# PCM5102a.net
KiCad netlist of a schematic drawn in EAGLE
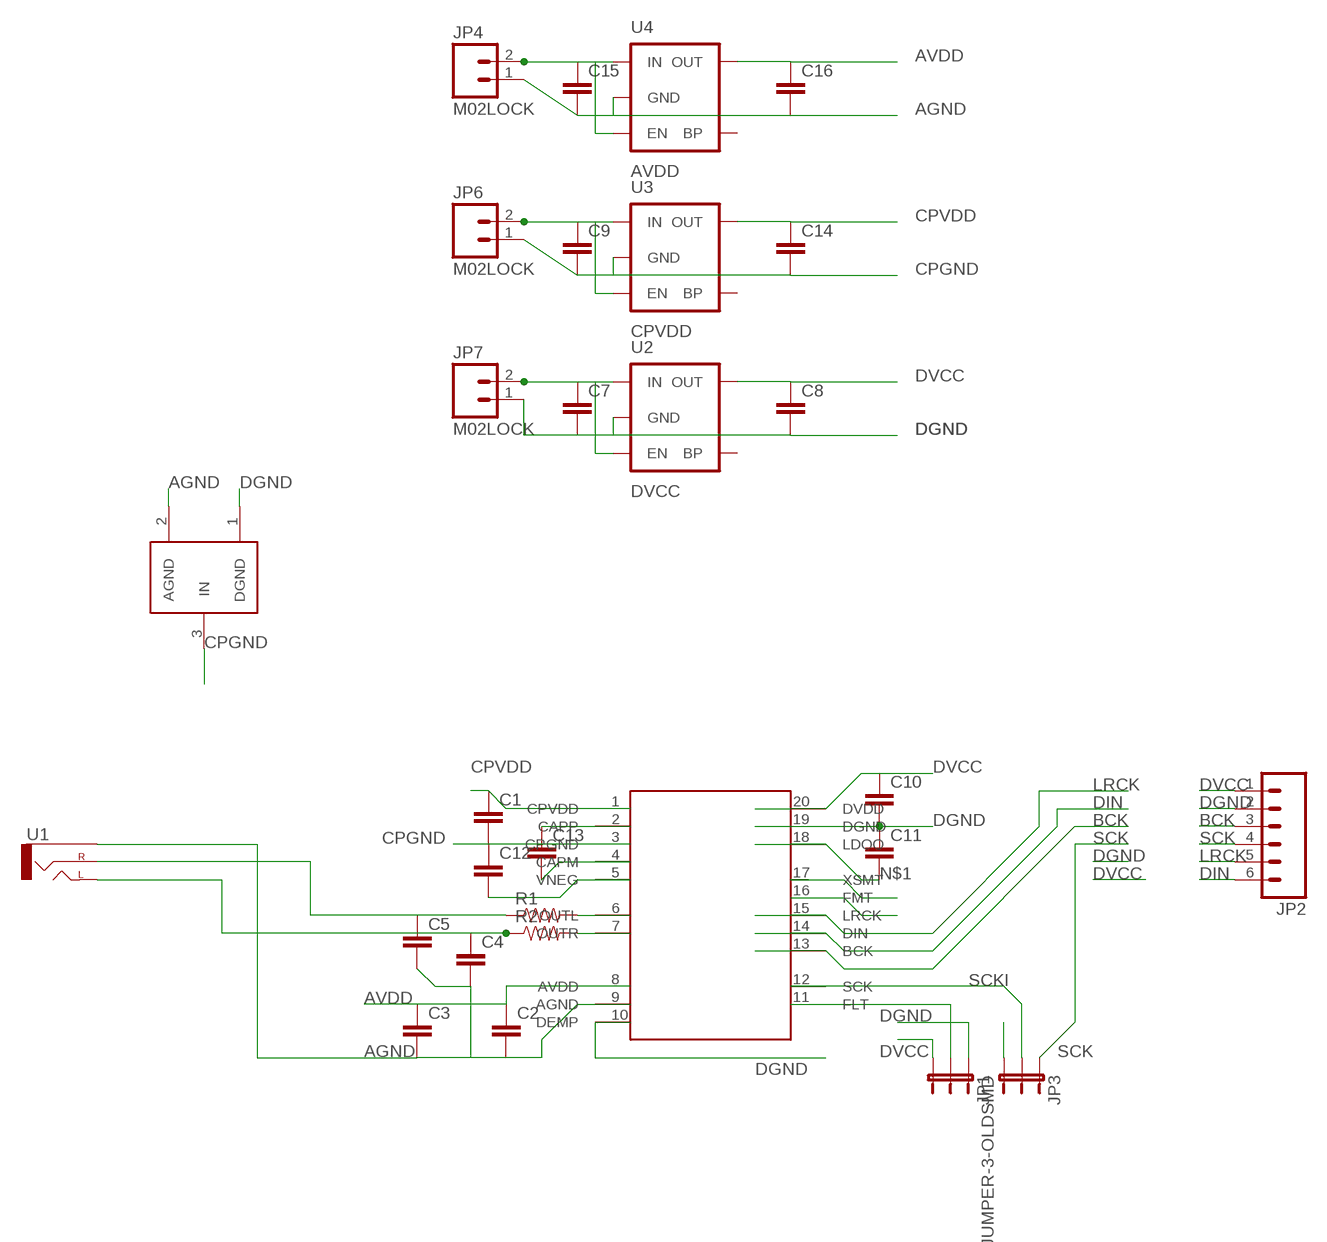
[diagram p0: schematic, sheet 1]

(export (version "E")
  (design (tool "Eeschema 10.0.6"))
  (components
    (comp (ref "C1")
      (value "CAP0805")
      (footprint "eagle-import:0805")
      (libsource (lib "eagle-import") (part "CAP0805"))
    )
    (comp (ref "C2")
      (value "CAP0805")
      (footprint "eagle-import:0805")
      (libsource (lib "eagle-import") (part "CAP0805"))
    )
    (comp (ref "C3")
      (value "CAP0805")
      (footprint "eagle-import:0805")
      (libsource (lib "eagle-import") (part "CAP0805"))
    )
    (comp (ref "C4")
      (value "CAPPTH1")
      (footprint "eagle-import:CAP-PTH-5MM")
      (libsource (lib "eagle-import") (part "CAPPTH1"))
    )
    (comp (ref "C5")
      (value "CAPPTH1")
      (footprint "eagle-import:CAP-PTH-5MM")
      (libsource (lib "eagle-import") (part "CAPPTH1"))
    )
    (comp (ref "C7")
      (value "CAP0805")
      (footprint "eagle-import:0805")
      (libsource (lib "eagle-import") (part "CAP0805"))
    )
    (comp (ref "C8")
      (value "CAP0805")
      (footprint "eagle-import:0805")
      (libsource (lib "eagle-import") (part "CAP0805"))
    )
    (comp (ref "C9")
      (value "CAP0805")
      (footprint "eagle-import:0805")
      (libsource (lib "eagle-import") (part "CAP0805"))
    )
    (comp (ref "C10")
      (value "CAP0805")
      (footprint "eagle-import:0805")
      (libsource (lib "eagle-import") (part "CAP0805"))
    )
    (comp (ref "C11")
      (value "CAP0805")
      (footprint "eagle-import:0805")
      (libsource (lib "eagle-import") (part "CAP0805"))
    )
    (comp (ref "C12")
      (value "CAP0805")
      (footprint "eagle-import:0805")
      (libsource (lib "eagle-import") (part "CAP0805"))
    )
    (comp (ref "C13")
      (value "CAP0805")
      (footprint "eagle-import:0805")
      (libsource (lib "eagle-import") (part "CAP0805"))
    )
    (comp (ref "C14")
      (value "CAP0805")
      (footprint "eagle-import:0805")
      (libsource (lib "eagle-import") (part "CAP0805"))
    )
    (comp (ref "C15")
      (value "CAP0805")
      (footprint "eagle-import:0805")
      (libsource (lib "eagle-import") (part "CAP0805"))
    )
    (comp (ref "C16")
      (value "CAP0805")
      (footprint "eagle-import:0805")
      (libsource (lib "eagle-import") (part "CAP0805"))
    )
    (comp (ref "JP1")
      (value "JUMPER-3-OLDPTH")
      (footprint "eagle-import:1X03")
      (libsource (lib "eagle-import") (part "JUMPER-3-OLDPTH"))
    )
    (comp (ref "JP2")
      (value "M06LOCK")
      (footprint "eagle-import:1X06_LOCK")
      (libsource (lib "eagle-import") (part "M06LOCK"))
    )
    (comp (ref "JP3")
      (value "JUMPER-3-OLDSMD")
      (footprint "eagle-import:SJ_3")
      (libsource (lib "eagle-import") (part "JUMPER-3-OLDSMD"))
    )
    (comp (ref "JP4")
      (value "M02LOCK")
      (footprint "eagle-import:1X02_LOCK")
      (libsource (lib "eagle-import") (part "M02LOCK"))
    )
    (comp (ref "JP6")
      (value "M02LOCK")
      (footprint "eagle-import:1X02_LOCK")
      (libsource (lib "eagle-import") (part "M02LOCK"))
    )
    (comp (ref "JP7")
      (value "M02LOCK")
      (footprint "eagle-import:1X02_LOCK")
      (libsource (lib "eagle-import") (part "M02LOCK"))
    )
    (comp (ref "R1")
      (value "RESISTORPTH-1/4W")
      (footprint "eagle-import:AXIAL-0.4")
      (libsource (lib "eagle-import") (part "RESISTORPTH-1/4W"))
    )
    (comp (ref "R2")
      (value "RESISTORPTH-1/4W")
      (footprint "eagle-import:AXIAL-0.4")
      (libsource (lib "eagle-import") (part "RESISTORPTH-1/4W"))
    )
    (comp (ref "U$1")
      (value "PCM5102")
      (footprint "eagle-import:TSSOP20")
      (libsource (lib "eagle-import") (part "PCM5102"))
    )
    (comp (ref "U$2")
      (value "GND_CONNECT")
      (footprint "eagle-import:GND_CONNECT")
      (libsource (lib "eagle-import") (part "GND_CONNECT"))
    )
    (comp (ref "U1")
      (value "AUDIO-JACKPTH")
      (footprint "eagle-import:AUDIO-JACK")
      (libsource (lib "eagle-import") (part "AUDIO-JACKPTH"))
    )
    (comp (ref "U2")
      (value "DVCC")
      (footprint "eagle-import:SOT23-5")
      (libsource (lib "eagle-import") (part "V_REG_LDOSMD"))
    )
    (comp (ref "U3")
      (value "CPVDD")
      (footprint "eagle-import:SOT23-5")
      (libsource (lib "eagle-import") (part "V_REG_LDOSMD"))
    )
    (comp (ref "U4")
      (value "AVDD")
      (footprint "eagle-import:SOT23-5")
      (libsource (lib "eagle-import") (part "V_REG_LDOSMD"))
    )
  )
  (nets
    (net (code "1") (name "/AGND") (class "Default")
      (node (ref "C15") (pin "2") (pinfunction "2_2") (pintype "passive"))
      (node (ref "C16") (pin "2") (pinfunction "2_2") (pintype "passive"))
      (node (ref "C2") (pin "2") (pinfunction "2_2") (pintype "passive"))
      (node (ref "C3") (pin "2") (pinfunction "2_2") (pintype "passive"))
      (node (ref "C4") (pin "2") (pinfunction "2_2") (pintype "passive"))
      (node (ref "C5") (pin "2") (pinfunction "2_2") (pintype "passive"))
      (node (ref "JP4") (pin "1") (pinfunction "1_1") (pintype "passive"))
      (node (ref "U$1") (pin "9") (pinfunction "AGND_9") (pintype "bidirectional"))
      (node (ref "U$2") (pin "2") (pinfunction "AGND_2") (pintype "bidirectional"))
      (node (ref "U1") (pin "SLEEVE") (pinfunction "SLEEVE_SLEEVE") (pintype "bidirectional"))
      (node (ref "U4") (pin "2") (pinfunction "GND_2") (pintype "input"))
    )
    (net (code "2") (name "/AVDD") (class "Default")
      (node (ref "C16") (pin "1") (pinfunction "1_1") (pintype "passive"))
      (node (ref "C2") (pin "1") (pinfunction "1_1") (pintype "passive"))
      (node (ref "C3") (pin "1") (pinfunction "1_1") (pintype "passive"))
      (node (ref "U$1") (pin "8") (pinfunction "AVDD_8") (pintype "bidirectional"))
      (node (ref "U4") (pin "5") (pinfunction "OUT_5") (pintype "passive"))
    )
    (net (code "3") (name "/BCK") (class "Default")
      (node (ref "JP2") (pin "3") (pinfunction "3_3") (pintype "passive"))
      (node (ref "U$1") (pin "13") (pinfunction "BCK_13") (pintype "bidirectional"))
    )
    (net (code "4") (name "/CPGND") (class "Default")
      (node (ref "C1") (pin "2") (pinfunction "2_2") (pintype "passive"))
      (node (ref "C12") (pin "1") (pinfunction "1_1") (pintype "passive"))
      (node (ref "C14") (pin "2") (pinfunction "2_2") (pintype "passive"))
      (node (ref "C9") (pin "2") (pinfunction "2_2") (pintype "passive"))
      (node (ref "JP6") (pin "1") (pinfunction "1_1") (pintype "passive"))
      (node (ref "U$1") (pin "3") (pinfunction "CPGND_3") (pintype "bidirectional"))
      (node (ref "U$2") (pin "3") (pinfunction "IN_3") (pintype "bidirectional"))
      (node (ref "U3") (pin "2") (pinfunction "GND_2") (pintype "input"))
    )
    (net (code "5") (name "/CPVDD") (class "Default")
      (node (ref "C1") (pin "1") (pinfunction "1_1") (pintype "passive"))
      (node (ref "C14") (pin "1") (pinfunction "1_1") (pintype "passive"))
      (node (ref "U$1") (pin "1") (pinfunction "CPVDD_1") (pintype "bidirectional"))
      (node (ref "U3") (pin "5") (pinfunction "OUT_5") (pintype "passive"))
    )
    (net (code "6") (name "/DGND") (class "Default")
      (node (ref "C10") (pin "2") (pinfunction "2_2") (pintype "passive"))
      (node (ref "C11") (pin "1") (pinfunction "1_1") (pintype "passive"))
      (node (ref "C7") (pin "2") (pinfunction "2_2") (pintype "passive"))
      (node (ref "C8") (pin "2") (pinfunction "2_2") (pintype "passive"))
      (node (ref "JP1") (pin "1") (pinfunction "1_1") (pintype "passive"))
      (node (ref "JP2") (pin "2") (pinfunction "2_2") (pintype "passive"))
      (node (ref "JP3") (pin "3") (pinfunction "3_3") (pintype "passive"))
      (node (ref "JP7") (pin "1") (pinfunction "1_1") (pintype "passive"))
      (node (ref "U$1") (pin "10") (pinfunction "DEMP_10") (pintype "bidirectional"))
      (node (ref "U$1") (pin "16") (pinfunction "FMT_16") (pintype "bidirectional"))
      (node (ref "U$1") (pin "19") (pinfunction "DGND_19") (pintype "bidirectional"))
      (node (ref "U$2") (pin "1") (pinfunction "DGND_1") (pintype "bidirectional"))
      (node (ref "U2") (pin "2") (pinfunction "GND_2") (pintype "input"))
    )
    (net (code "7") (name "/DIN") (class "Default")
      (node (ref "JP2") (pin "6") (pinfunction "6_6") (pintype "passive"))
      (node (ref "U$1") (pin "14") (pinfunction "DIN_14") (pintype "bidirectional"))
    )
    (net (code "8") (name "/DVCC") (class "Default")
      (node (ref "C10") (pin "1") (pinfunction "1_1") (pintype "passive"))
      (node (ref "C8") (pin "1") (pinfunction "1_1") (pintype "passive"))
      (node (ref "JP1") (pin "3") (pinfunction "3_3") (pintype "passive"))
      (node (ref "JP2") (pin "1") (pinfunction "1_1") (pintype "passive"))
      (node (ref "U$1") (pin "17") (pinfunction "XSMT_17") (pintype "bidirectional"))
      (node (ref "U$1") (pin "20") (pinfunction "DVDD_20") (pintype "bidirectional"))
      (node (ref "U2") (pin "5") (pinfunction "OUT_5") (pintype "passive"))
    )
    (net (code "9") (name "/LRCK") (class "Default")
      (node (ref "JP2") (pin "5") (pinfunction "5_5") (pintype "passive"))
      (node (ref "U$1") (pin "15") (pinfunction "LRCK_15") (pintype "bidirectional"))
    )
    (net (code "10") (name "/N$1") (class "Default")
      (node (ref "C11") (pin "2") (pinfunction "2_2") (pintype "passive"))
      (node (ref "U$1") (pin "18") (pinfunction "LDOO_18") (pintype "bidirectional"))
    )
    (net (code "11") (name "/SCK") (class "Default")
      (node (ref "JP2") (pin "4") (pinfunction "4_4") (pintype "passive"))
      (node (ref "JP3") (pin "1") (pinfunction "1_1") (pintype "passive"))
    )
    (net (code "12") (name "/SCKI") (class "Default")
      (node (ref "JP3") (pin "2") (pinfunction "2_2") (pintype "passive"))
      (node (ref "U$1") (pin "12") (pinfunction "SCK_12") (pintype "bidirectional"))
    )
    (net (code "13") (name "Net-(R1-1)") (class "Default")
      (node (ref "C5") (pin "1") (pinfunction "1_1") (pintype "passive"))
      (node (ref "R1") (pin "P$1") (pinfunction "1_P$1") (pintype "passive"))
      (node (ref "U1") (pin "RING") (pinfunction "RIGHT_RING") (pintype "bidirectional"))
    )
    (net (code "14") (name "Net-(R1-2)") (class "Default")
      (node (ref "R1") (pin "P$2") (pinfunction "2_P$2") (pintype "passive"))
      (node (ref "U$1") (pin "6") (pinfunction "OUTL_6") (pintype "bidirectional"))
    )
    (net (code "15") (name "Net-(R2-1)") (class "Default")
      (node (ref "C4") (pin "1") (pinfunction "1_1") (pintype "passive"))
      (node (ref "R2") (pin "P$1") (pinfunction "1_P$1") (pintype "passive"))
      (node (ref "U1") (pin "TIP") (pinfunction "LEFT_TIP") (pintype "bidirectional"))
    )
    (net (code "16") (name "Net-(R2-2)") (class "Default")
      (node (ref "R2") (pin "P$2") (pinfunction "2_P$2") (pintype "passive"))
      (node (ref "U$1") (pin "7") (pinfunction "OUTR_7") (pintype "bidirectional"))
    )
    (net (code "17") (name "Net-(U$1-CAPM)") (class "Default")
      (node (ref "C13") (pin "2") (pinfunction "2_2") (pintype "passive"))
      (node (ref "U$1") (pin "4") (pinfunction "CAPM_4") (pintype "bidirectional"))
    )
    (net (code "18") (name "Net-(U$1-CAPP)") (class "Default")
      (node (ref "C13") (pin "1") (pinfunction "1_1") (pintype "passive"))
      (node (ref "U$1") (pin "2") (pinfunction "CAPP_2") (pintype "bidirectional"))
    )
    (net (code "19") (name "Net-(U$1-FLT)") (class "Default")
      (node (ref "JP1") (pin "2") (pinfunction "2_2") (pintype "passive"))
      (node (ref "U$1") (pin "11") (pinfunction "FLT_11") (pintype "bidirectional"))
    )
    (net (code "20") (name "Net-(U$1-VNEG)") (class "Default")
      (node (ref "C12") (pin "2") (pinfunction "2_2") (pintype "passive"))
      (node (ref "U$1") (pin "5") (pinfunction "VNEG_5") (pintype "bidirectional"))
    )
    (net (code "21") (name "Net-(U2-EN)") (class "Default")
      (node (ref "C7") (pin "1") (pinfunction "1_1") (pintype "passive"))
      (node (ref "JP7") (pin "2") (pinfunction "2_2") (pintype "passive"))
      (node (ref "U2") (pin "1") (pinfunction "IN_1") (pintype "input"))
      (node (ref "U2") (pin "3") (pinfunction "EN_3") (pintype "input"))
    )
    (net (code "22") (name "Net-(U3-EN)") (class "Default")
      (node (ref "C9") (pin "1") (pinfunction "1_1") (pintype "passive"))
      (node (ref "JP6") (pin "2") (pinfunction "2_2") (pintype "passive"))
      (node (ref "U3") (pin "1") (pinfunction "IN_1") (pintype "input"))
      (node (ref "U3") (pin "3") (pinfunction "EN_3") (pintype "input"))
    )
    (net (code "23") (name "Net-(U4-EN)") (class "Default")
      (node (ref "C15") (pin "1") (pinfunction "1_1") (pintype "passive"))
      (node (ref "JP4") (pin "2") (pinfunction "2_2") (pintype "passive"))
      (node (ref "U4") (pin "1") (pinfunction "IN_1") (pintype "input"))
      (node (ref "U4") (pin "3") (pinfunction "EN_3") (pintype "input"))
    )
    (net (code "24") (name "unconnected-(U2-BP-Pad4)") (class "Default")
      (node (ref "U2") (pin "4") (pinfunction "BP_4") (pintype "input"))
    )
    (net (code "25") (name "unconnected-(U3-BP-Pad4)") (class "Default")
      (node (ref "U3") (pin "4") (pinfunction "BP_4") (pintype "input"))
    )
    (net (code "26") (name "unconnected-(U4-BP-Pad4)") (class "Default")
      (node (ref "U4") (pin "4") (pinfunction "BP_4") (pintype "input"))
    )
  )
)
